# Schematic.net
KiCad netlist of a schematic drawn in EasyEDA
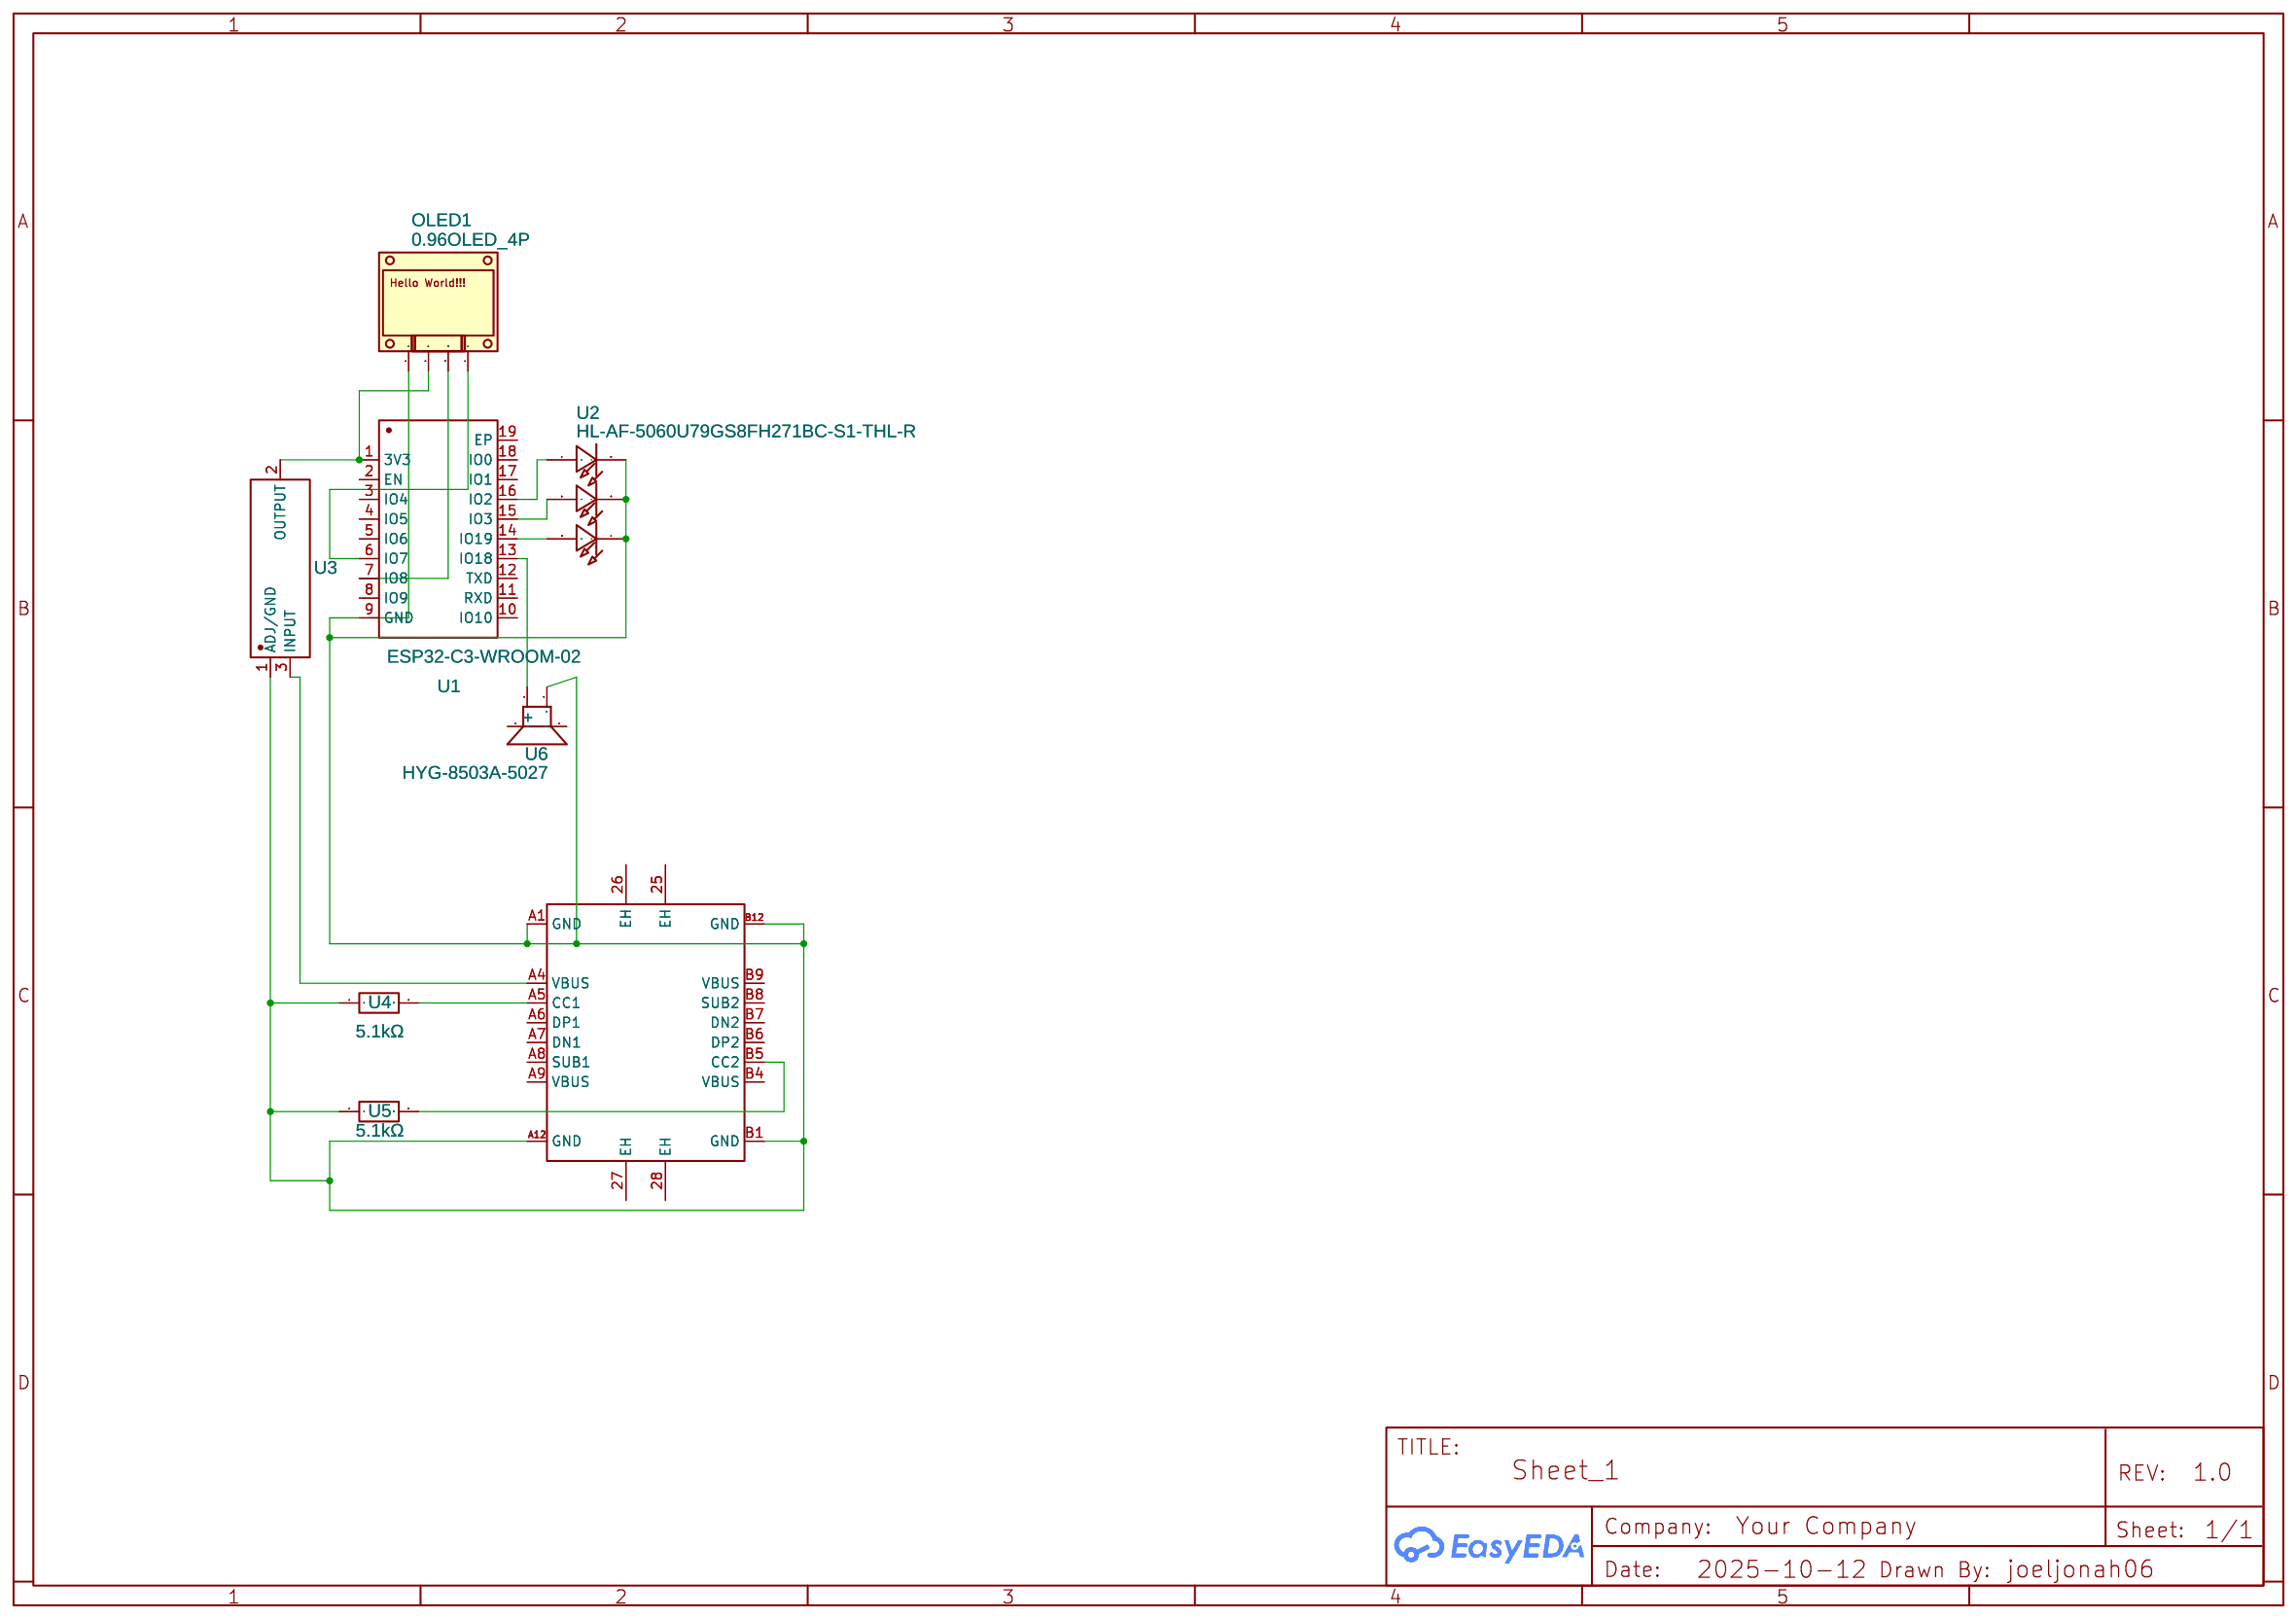
[diagram p0: schematic sheet]

(export (version "E")
  (design (tool "Eeschema 10.0.6"))
  (components
    (comp (ref "OLED1") (value "0.96OLED_4P") (libsource (lib "") (part "0.96OLED_4P")))
    (comp (ref "U1")
      (value "ESP32-C3-WROOM-02")
      (fields
        (field (name "Manufacturer Part") "ESP32-C3-WROOM-02-N4")
        (field (name "Manufacturer") "ESPRESSIF(乐鑫)")
      )
      (libsource (lib "") (part "ESP32-C3-WROOM-02-N4(4MB)"))
    )
    (comp (ref "U2")
      (value "HL-AF-5060U79GS8FH271BC-S1-THL-R")
      (fields (field (name "Manufacturer") "HONGLITRONIC(鸿利光电)"))
      (libsource (lib "") (part "HL-AF-5060U79GS8FH271BC-S1-THL-R"))
    )
    (comp (ref "U3")
      (value "AMS1117-3.3_C41414107")
      (fields (field (name "Manufacturer Part") "AMS1117-3.3") (field (name "Manufacturer") "YONGYUTAI(永裕泰)"))
      (libsource (lib "") (part "AMS1117-3.3_C41414107"))
    )
    (comp (ref "U4")
      (value "5.1kΩ")
      (fields (field (name "Manufacturer Part") "FRC0805J512TS") (field (name "Manufacturer") "FOJAN(富捷)"))
      (libsource (lib "") (part "FRC0805J512TS"))
    )
    (comp (ref "U5")
      (value "5.1kΩ")
      (fields (field (name "Manufacturer Part") "FRC0805J512TS") (field (name "Manufacturer") "FOJAN(富捷)"))
      (libsource (lib "") (part "FRC0805J512TS"))
    )
    (comp (ref "U6")
      (value "HYG-8503A-5027")
      (fields (field (name "Manufacturer") "HYDZ(华宇)"))
      (libsource (lib "") (part "HYG-8503A-5027"))
    )
    (comp (ref "USB1")
      (value "TYPE-C 16P CB1.6 073")
      (fields (field (name "Manufacturer") "SHOU HAN(首韩)"))
      (libsource (lib "") (part "TYPE-C 16P CB1.6 073"))
    )
  )
  (nets
    (net (code "1") (name "Net-(U1-3V3)") (class "Default")
      (node (ref "OLED1") (pin "2") (pinfunction "2_2") (pintype "unspecified"))
      (node (ref "U1") (pin "1") (pinfunction "3V3_1") (pintype "unspecified"))
      (node (ref "U3") (pin "2") (pinfunction "OUTPUT_2") (pintype "unspecified"))
    )
    (net (code "2") (name "Net-(U1-GND)") (class "Default")
      (node (ref "U1") (pin "9") (pinfunction "GND_9") (pintype "unspecified"))
      (node (ref "U2") (pin "1") (pinfunction "-_1") (pintype "unspecified"))
      (node (ref "U2") (pin "2") (pinfunction "-_2") (pintype "unspecified"))
      (node (ref "U2") (pin "3") (pinfunction "-_3") (pintype "unspecified"))
      (node (ref "U3") (pin "1") (pinfunction "ADJ/GND_1") (pintype "unspecified"))
      (node (ref "U4") (pin "1") (pinfunction "1_1") (pintype "unspecified"))
      (node (ref "U5") (pin "1") (pinfunction "1_1") (pintype "unspecified"))
      (node (ref "U6") (pin "2") (pinfunction "2_2") (pintype "unspecified"))
      (node (ref "USB1") (pin "A1") (pinfunction "GND_A1") (pintype "unspecified"))
      (node (ref "USB1") (pin "A12") (pinfunction "GND_A12") (pintype "unspecified"))
      (node (ref "USB1") (pin "B1") (pinfunction "GND_B1") (pintype "unspecified"))
      (node (ref "USB1") (pin "B12") (pinfunction "GND_B12") (pintype "unspecified"))
    )
    (net (code "3") (name "Net-(U1-IO2)") (class "Default")
      (node (ref "U1") (pin "16") (pinfunction "IO2_16") (pintype "unspecified"))
      (node (ref "U2") (pin "4") (pinfunction "+_4") (pintype "unspecified"))
    )
    (net (code "4") (name "Net-(U1-IO3)") (class "Default")
      (node (ref "U1") (pin "15") (pinfunction "IO3_15") (pintype "unspecified"))
      (node (ref "U2") (pin "5") (pinfunction "+_5") (pintype "unspecified"))
    )
    (net (code "5") (name "Net-(U1-IO7)") (class "Default")
      (node (ref "OLED1") (pin "4") (pinfunction "4_4") (pintype "unspecified"))
      (node (ref "U1") (pin "6") (pinfunction "IO7_6") (pintype "unspecified"))
    )
    (net (code "6") (name "Net-(U1-IO8)") (class "Default")
      (node (ref "OLED1") (pin "3") (pinfunction "3_3") (pintype "unspecified"))
      (node (ref "U1") (pin "7") (pinfunction "IO8_7") (pintype "unspecified"))
    )
    (net (code "7") (name "Net-(U1-IO18)") (class "Default")
      (node (ref "U1") (pin "13") (pinfunction "IO18_13") (pintype "unspecified"))
      (node (ref "U6") (pin "1") (pinfunction "+_1") (pintype "unspecified"))
    )
    (net (code "8") (name "Net-(U1-IO19)") (class "Default")
      (node (ref "U1") (pin "14") (pinfunction "IO19_14") (pintype "unspecified"))
      (node (ref "U2") (pin "6") (pinfunction "+_6") (pintype "unspecified"))
    )
    (net (code "9") (name "Net-(U3-INPUT)") (class "Default")
      (node (ref "U3") (pin "3") (pinfunction "INPUT_3") (pintype "unspecified"))
      (node (ref "USB1") (pin "A4") (pinfunction "VBUS_A4") (pintype "unspecified"))
    )
    (net (code "10") (name "Net-(USB1-CC1)") (class "Default")
      (node (ref "U4") (pin "2") (pinfunction "2_2") (pintype "unspecified"))
      (node (ref "USB1") (pin "A5") (pinfunction "CC1_A5") (pintype "unspecified"))
    )
    (net (code "11") (name "Net-(USB1-CC2)") (class "Default")
      (node (ref "U5") (pin "2") (pinfunction "2_2") (pintype "unspecified"))
      (node (ref "USB1") (pin "B5") (pinfunction "CC2_B5") (pintype "unspecified"))
    )
    (net (code "12") (name "unconnected-(OLED1-Pad1)") (class "Default")
      (node (ref "OLED1") (pin "1") (pinfunction "1_1") (pintype "unspecified"))
    )
    (net (code "13") (name "unconnected-(U1-EN-Pad2)") (class "Default")
      (node (ref "U1") (pin "2") (pinfunction "EN_2") (pintype "unspecified"))
    )
    (net (code "14") (name "unconnected-(U1-EP-Pad19)") (class "Default")
      (node (ref "U1") (pin "19") (pinfunction "EP_19") (pintype "unspecified"))
    )
    (net (code "15") (name "unconnected-(U1-IO0-Pad18)") (class "Default")
      (node (ref "U1") (pin "18") (pinfunction "IO0_18") (pintype "unspecified"))
    )
    (net (code "16") (name "unconnected-(U1-IO1-Pad17)") (class "Default")
      (node (ref "U1") (pin "17") (pinfunction "IO1_17") (pintype "unspecified"))
    )
    (net (code "17") (name "unconnected-(U1-IO4-Pad3)") (class "Default")
      (node (ref "U1") (pin "3") (pinfunction "IO4_3") (pintype "unspecified"))
    )
    (net (code "18") (name "unconnected-(U1-IO5-Pad4)") (class "Default")
      (node (ref "U1") (pin "4") (pinfunction "IO5_4") (pintype "unspecified"))
    )
    (net (code "19") (name "unconnected-(U1-IO6-Pad5)") (class "Default")
      (node (ref "U1") (pin "5") (pinfunction "IO6_5") (pintype "unspecified"))
    )
    (net (code "20") (name "unconnected-(U1-IO9-Pad8)") (class "Default")
      (node (ref "U1") (pin "8") (pinfunction "IO9_8") (pintype "unspecified"))
    )
    (net (code "21") (name "unconnected-(U1-IO10-Pad10)") (class "Default")
      (node (ref "U1") (pin "10") (pinfunction "IO10_10") (pintype "unspecified"))
    )
    (net (code "22") (name "unconnected-(U1-RXD-Pad11)") (class "Default")
      (node (ref "U1") (pin "11") (pinfunction "RXD_11") (pintype "unspecified"))
    )
    (net (code "23") (name "unconnected-(U1-TXD-Pad12)") (class "Default")
      (node (ref "U1") (pin "12") (pinfunction "TXD_12") (pintype "unspecified"))
    )
    (net (code "24") (name "unconnected-(U6-Pad3)") (class "Default")
      (node (ref "U6") (pin "3") (pinfunction "3_3") (pintype "unspecified"))
    )
    (net (code "25") (name "unconnected-(U6-Pad4)") (class "Default")
      (node (ref "U6") (pin "4") (pinfunction "4_4") (pintype "unspecified"))
    )
    (net (code "26") (name "unconnected-(USB1-DN1-PadA7)") (class "Default")
      (node (ref "USB1") (pin "A7") (pinfunction "DN1_A7") (pintype "unspecified"))
    )
    (net (code "27") (name "unconnected-(USB1-DN2-PadB7)") (class "Default")
      (node (ref "USB1") (pin "B7") (pinfunction "DN2_B7") (pintype "unspecified"))
    )
    (net (code "28") (name "unconnected-(USB1-DP1-PadA6)") (class "Default")
      (node (ref "USB1") (pin "A6") (pinfunction "DP1_A6") (pintype "unspecified"))
    )
    (net (code "29") (name "unconnected-(USB1-DP2-PadB6)") (class "Default")
      (node (ref "USB1") (pin "B6") (pinfunction "DP2_B6") (pintype "unspecified"))
    )
    (net (code "30") (name "unconnected-(USB1-EH-Pad25)") (class "Default")
      (node (ref "USB1") (pin "25") (pinfunction "EH_25") (pintype "unspecified"))
    )
    (net (code "31") (name "unconnected-(USB1-EH-Pad26)") (class "Default")
      (node (ref "USB1") (pin "26") (pinfunction "EH_26") (pintype "unspecified"))
    )
    (net (code "32") (name "unconnected-(USB1-EH-Pad27)") (class "Default")
      (node (ref "USB1") (pin "27") (pinfunction "EH_27") (pintype "unspecified"))
    )
    (net (code "33") (name "unconnected-(USB1-EH-Pad28)") (class "Default")
      (node (ref "USB1") (pin "28") (pinfunction "EH_28") (pintype "unspecified"))
    )
    (net (code "34") (name "unconnected-(USB1-SUB1-PadA8)") (class "Default")
      (node (ref "USB1") (pin "A8") (pinfunction "SUB1_A8") (pintype "unspecified"))
    )
    (net (code "35") (name "unconnected-(USB1-SUB2-PadB8)") (class "Default")
      (node (ref "USB1") (pin "B8") (pinfunction "SUB2_B8") (pintype "unspecified"))
    )
    (net (code "36") (name "unconnected-(USB1-VBUS-PadA9)") (class "Default")
      (node (ref "USB1") (pin "A9") (pinfunction "VBUS_A9") (pintype "unspecified"))
    )
    (net (code "37") (name "unconnected-(USB1-VBUS-PadB4)") (class "Default")
      (node (ref "USB1") (pin "B4") (pinfunction "VBUS_B4") (pintype "unspecified"))
    )
    (net (code "38") (name "unconnected-(USB1-VBUS-PadB9)") (class "Default")
      (node (ref "USB1") (pin "B9") (pinfunction "VBUS_B9") (pintype "unspecified"))
    )
  )
)
